# Project_Canary_V4_5.net
KiCad netlist of a schematic drawn in EAGLE
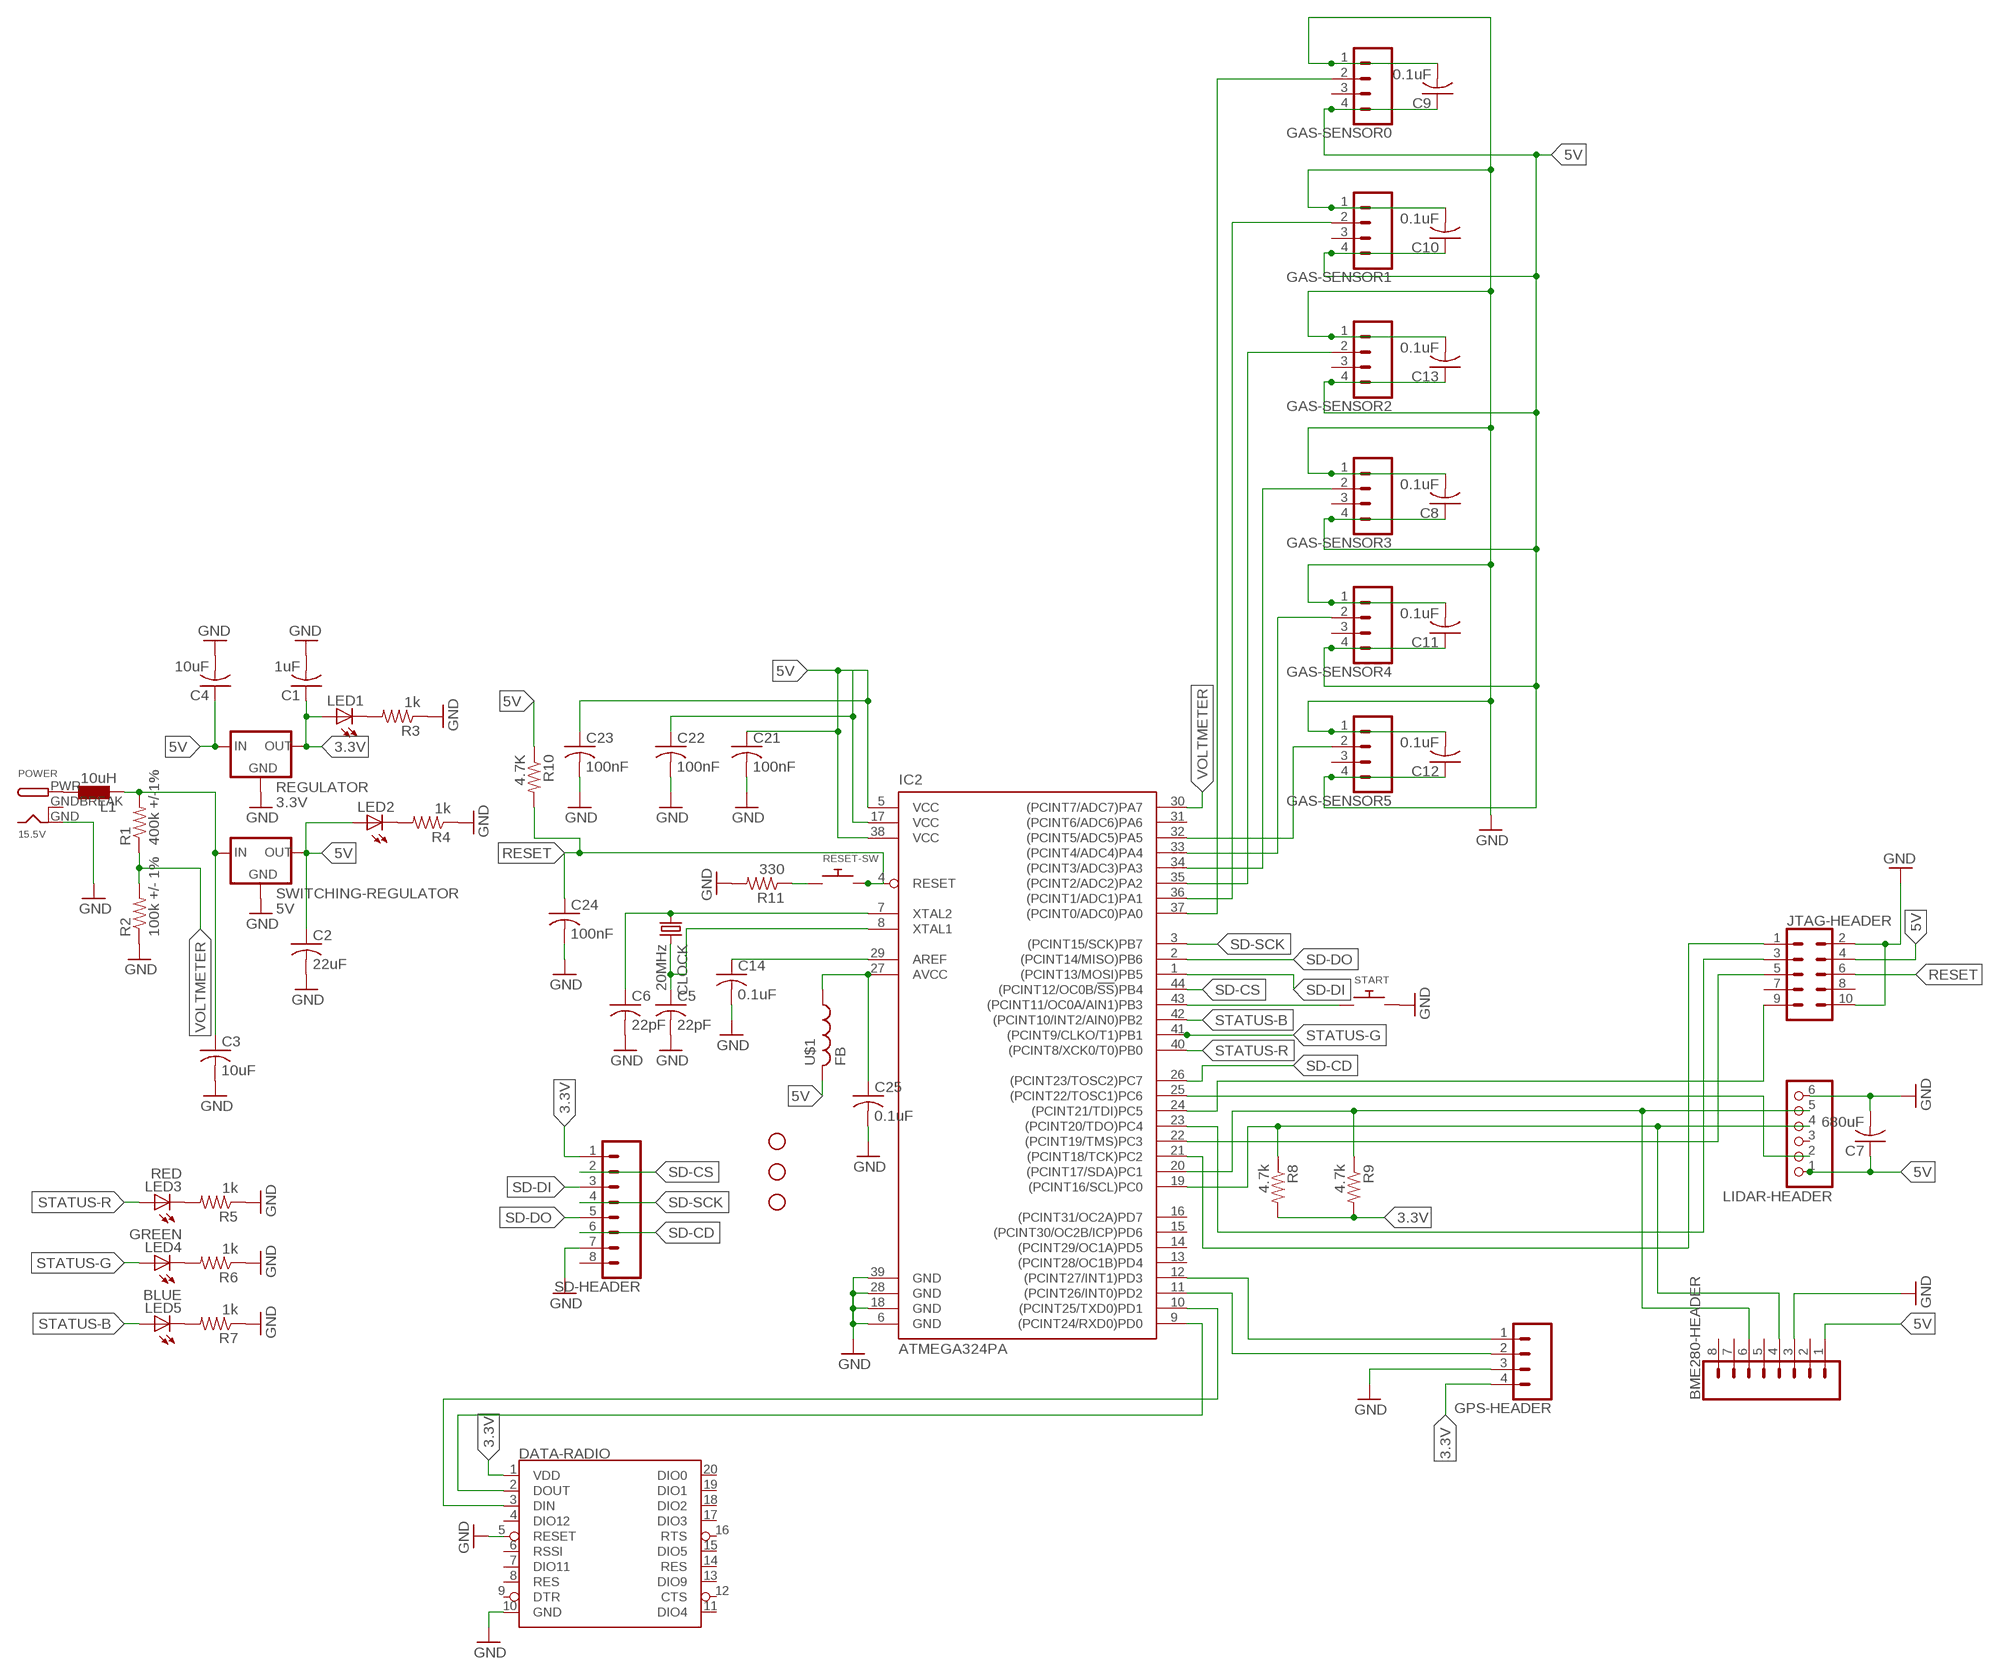
[diagram p0: schematic, sheet 1]

(export (version "E")
  (design (tool "Eeschema 10.0.6"))
  (components
    (comp (ref "BME280-HEADER")
      (value "CONN_08\"")
      (footprint "eagle-import:1X08")
      (libsource (lib "eagle-import") (part "CONN_08{dblquote}"))
    )
    (comp (ref "C1")
      (value "1uF")
      (footprint "eagle-import:C0805")
      (libsource (lib "eagle-import") (part "C-USC0805"))
    )
    (comp (ref "C2")
      (value "22uF")
      (footprint "eagle-import:C0603")
      (libsource (lib "eagle-import") (part "C-USC0603"))
    )
    (comp (ref "C3")
      (value "10uF")
      (footprint "eagle-import:C0805")
      (libsource (lib "eagle-import") (part "C-USC0805"))
    )
    (comp (ref "C4")
      (value "10uF")
      (footprint "eagle-import:C0603")
      (libsource (lib "eagle-import") (part "C-USC0603"))
    )
    (comp (ref "C5")
      (value "22pF")
      (footprint "eagle-import:C0603")
      (libsource (lib "eagle-import") (part "C-USC0603"))
    )
    (comp (ref "C6")
      (value "22pF")
      (footprint "eagle-import:C0603")
      (libsource (lib "eagle-import") (part "C-USC0603"))
    )
    (comp (ref "C7")
      (value "680uF")
      (footprint "eagle-import:C0603")
      (libsource (lib "eagle-import") (part "C-USC0603"))
    )
    (comp (ref "C8")
      (value "0.1uF")
      (footprint "eagle-import:C0603")
      (libsource (lib "eagle-import") (part "C-USC0603"))
    )
    (comp (ref "C9")
      (value "0.1uF")
      (footprint "eagle-import:C0603")
      (libsource (lib "eagle-import") (part "C-USC0603"))
    )
    (comp (ref "C10")
      (value "0.1uF")
      (footprint "eagle-import:C0603")
      (libsource (lib "eagle-import") (part "C-USC0603"))
    )
    (comp (ref "C11")
      (value "0.1uF")
      (footprint "eagle-import:C0603")
      (libsource (lib "eagle-import") (part "C-USC0603"))
    )
    (comp (ref "C12")
      (value "0.1uF")
      (footprint "eagle-import:C0603")
      (libsource (lib "eagle-import") (part "C-USC0603"))
    )
    (comp (ref "C13")
      (value "0.1uF")
      (footprint "eagle-import:C0603")
      (libsource (lib "eagle-import") (part "C-USC0603"))
    )
    (comp (ref "C14")
      (value "0.1uF")
      (footprint "eagle-import:C0603")
      (libsource (lib "eagle-import") (part "C-USC0603"))
    )
    (comp (ref "C21")
      (value "100nF")
      (footprint "eagle-import:C0603")
      (libsource (lib "eagle-import") (part "C-USC0603"))
    )
    (comp (ref "C22")
      (value "100nF")
      (footprint "eagle-import:C0603")
      (libsource (lib "eagle-import") (part "C-USC0603"))
    )
    (comp (ref "C23")
      (value "100nF")
      (footprint "eagle-import:C0603")
      (libsource (lib "eagle-import") (part "C-USC0603"))
    )
    (comp (ref "C24")
      (value "100nF")
      (footprint "eagle-import:C0805")
      (libsource (lib "eagle-import") (part "C-USC0805"))
    )
    (comp (ref "C25")
      (value "0.1uF")
      (footprint "eagle-import:C0603")
      (libsource (lib "eagle-import") (part "C-USC0603"))
    )
    (comp (ref "CLOCK")
      (value "20MHz")
      (footprint "eagle-import:86SMX")
      (libsource (lib "eagle-import") (part "CRYSTAL68SMX"))
    )
    (comp (ref "DATA-RADIO")
      (value "XBEE")
      (footprint "eagle-import:XBEE")
      (libsource (lib "eagle-import") (part "XBEE"))
    )
    (comp (ref "GAS-SENSOR0")
      (value "CONN_04")
      (footprint "eagle-import:1X04")
      (libsource (lib "eagle-import") (part "CONN_04"))
    )
    (comp (ref "GAS-SENSOR1")
      (value "CONN_04")
      (footprint "eagle-import:1X04")
      (libsource (lib "eagle-import") (part "CONN_04"))
    )
    (comp (ref "GAS-SENSOR2")
      (value "CONN_04")
      (footprint "eagle-import:1X04")
      (libsource (lib "eagle-import") (part "CONN_04"))
    )
    (comp (ref "GAS-SENSOR3")
      (value "CONN_04")
      (footprint "eagle-import:1X04")
      (libsource (lib "eagle-import") (part "CONN_04"))
    )
    (comp (ref "GAS-SENSOR4")
      (value "CONN_04")
      (footprint "eagle-import:1X04")
      (libsource (lib "eagle-import") (part "CONN_04"))
    )
    (comp (ref "GAS-SENSOR5")
      (value "CONN_04")
      (footprint "eagle-import:1X04")
      (libsource (lib "eagle-import") (part "CONN_04"))
    )
    (comp (ref "GPS-HEADER")
      (value "CONN_04")
      (footprint "eagle-import:1X04")
      (libsource (lib "eagle-import") (part "CONN_04"))
    )
    (comp (ref "IC2")
      (value "ATMEGA324PA")
      (footprint "eagle-import:TQFP44")
      (fields (field (name "MPN") "ATMEGA644PV-10AU"))
      (libsource (lib "eagle-import") (part "ATMEGA644A"))
    )
    (comp (ref "JTAG-HEADER")
      (value "CONN_05X2PTH")
      (footprint "eagle-import:2X5")
      (libsource (lib "eagle-import") (part "CONN_05X2PTH"))
    )
    (comp (ref "L1")
      (value "10uH")
      (footprint "eagle-import:L1812")
      (libsource (lib "eagle-import") (part "L"))
    )
    (comp (ref "LED1")
      (value "LEDCHIP-LED0805")
      (footprint "eagle-import:CHIP-LED0805")
      (libsource (lib "eagle-import") (part "LEDCHIP-LED0805"))
    )
    (comp (ref "LED2")
      (value "LEDCHIP-LED0805")
      (footprint "eagle-import:CHIP-LED0805")
      (libsource (lib "eagle-import") (part "LEDCHIP-LED0805"))
    )
    (comp (ref "LED3")
      (value "RED")
      (footprint "eagle-import:CHIP-LED0805")
      (libsource (lib "eagle-import") (part "LEDCHIP-LED0805"))
    )
    (comp (ref "LED4")
      (value "GREEN")
      (footprint "eagle-import:CHIP-LED0805")
      (libsource (lib "eagle-import") (part "LEDCHIP-LED0805"))
    )
    (comp (ref "LED5")
      (value "BLUE")
      (footprint "eagle-import:CHIP-LED0805")
      (libsource (lib "eagle-import") (part "LEDCHIP-LED0805"))
    )
    (comp (ref "LIDAR-HEADER")
      (value "PINHD-1X6")
      (footprint "eagle-import:1X06")
      (libsource (lib "eagle-import") (part "PINHD-1X6"))
    )
    (comp (ref "MOUNT-HOLE1")
      (value "STAND-OFF")
      (footprint "eagle-import:STAND-OFF")
      (libsource (lib "eagle-import") (part "STAND-OFF"))
    )
    (comp (ref "MOUNT-HOLE2")
      (value "STAND-OFF")
      (footprint "eagle-import:STAND-OFF")
      (libsource (lib "eagle-import") (part "STAND-OFF"))
    )
    (comp (ref "MOUNT-HOLE3")
      (value "STAND-OFF")
      (footprint "eagle-import:STAND-OFF")
      (libsource (lib "eagle-import") (part "STAND-OFF"))
    )
    (comp (ref "POWER")
      (value "15.5V")
      (footprint "eagle-import:DCJACK_2MM_PTH")
      (libsource (lib "eagle-import") (part "DCBARRELPTH"))
    )
    (comp (ref "R1")
      (value "400k +/-1%")
      (footprint "eagle-import:M0805")
      (libsource (lib "eagle-import") (part "R-US_M0805"))
    )
    (comp (ref "R2")
      (value "100k +/- 1%")
      (footprint "eagle-import:M0805")
      (libsource (lib "eagle-import") (part "R-US_M0805"))
    )
    (comp (ref "R3")
      (value "1k")
      (footprint "eagle-import:M0805")
      (libsource (lib "eagle-import") (part "R-US_M0805"))
    )
    (comp (ref "R4")
      (value "1k")
      (footprint "eagle-import:M0805")
      (libsource (lib "eagle-import") (part "R-US_M0805"))
    )
    (comp (ref "R5")
      (value "1k")
      (footprint "eagle-import:M0805")
      (libsource (lib "eagle-import") (part "R-US_M0805"))
    )
    (comp (ref "R6")
      (value "1k")
      (footprint "eagle-import:M0805")
      (libsource (lib "eagle-import") (part "R-US_M0805"))
    )
    (comp (ref "R7")
      (value "1k")
      (footprint "eagle-import:M0805")
      (libsource (lib "eagle-import") (part "R-US_M0805"))
    )
    (comp (ref "R8")
      (value "4.7k")
      (footprint "eagle-import:M0805")
      (libsource (lib "eagle-import") (part "R-US_M0805"))
    )
    (comp (ref "R9")
      (value "4.7k")
      (footprint "eagle-import:M0805")
      (libsource (lib "eagle-import") (part "R-US_M0805"))
    )
    (comp (ref "R10")
      (value "4.7K")
      (footprint "eagle-import:M0805")
      (libsource (lib "eagle-import") (part "R-US_M0805"))
    )
    (comp (ref "R11")
      (value "330")
      (footprint "eagle-import:M0805")
      (libsource (lib "eagle-import") (part "R-US_M0805"))
    )
    (comp (ref "REGULATOR")
      (value "3.3V")
      (footprint "eagle-import:TO220-IGO")
      (libsource (lib "eagle-import") (part "V_REG_78XXSINK"))
    )
    (comp (ref "RESET-SW")
      (value "SWITCH_PUSHBUTTONSOFTTOUCHSMD_SJ")
      (footprint "eagle-import:PUSHBUTTON_SMD_SJ")
      (libsource (lib "eagle-import") (part "SWITCH_PUSHBUTTONSOFTTOUCHSMD_SJ"))
    )
    (comp (ref "SD-HEADER")
      (value "CONN_08\"")
      (footprint "eagle-import:1X08")
      (libsource (lib "eagle-import") (part "CONN_08{dblquote}"))
    )
    (comp (ref "START")
      (value "SWITCH_PUSHBUTTONSOFTTOUCHSMD_SJ")
      (footprint "eagle-import:PUSHBUTTON_SMD_SJ")
      (libsource (lib "eagle-import") (part "SWITCH_PUSHBUTTONSOFTTOUCHSMD_SJ"))
    )
    (comp (ref "SWITCHING-REGULATOR")
      (value "5V")
      (footprint "eagle-import:TO220-IGO")
      (libsource (lib "eagle-import") (part "V_REG_78XXSINK"))
    )
    (comp (ref "U$1") (value "FB") (footprint "eagle-import:FB") (libsource (lib "eagle-import") (part "FB")))
  )
  (nets
    (net (code "1") (name "/GNDBREAK") (class "Default")
      (node (ref "POWER") (pin "GNDBREAK") (pinfunction "GNDBREAK_GNDBREAK") (pintype "power_in"))
    )
    (net (code "2") (name "3.3V") (class "Default")
      (node (ref "C1") (pin "1") (pinfunction "1_1") (pintype "passive"))
      (node (ref "DATA-RADIO") (pin "1") (pinfunction "VDD_1") (pintype "power_in"))
      (node (ref "GPS-HEADER") (pin "4") (pinfunction "4_4") (pintype "passive"))
      (node (ref "LED1") (pin "A") (pinfunction "A_A") (pintype "passive"))
      (node (ref "R8") (pin "2") (pinfunction "2_2") (pintype "passive"))
      (node (ref "R9") (pin "2") (pinfunction "2_2") (pintype "passive"))
      (node (ref "REGULATOR") (pin "OUT") (pinfunction "OUT_OUT") (pintype "passive"))
      (node (ref "SD-HEADER") (pin "1") (pinfunction "1_1") (pintype "passive"))
    )
    (net (code "3") (name "5V") (class "Default")
      (node (ref "BME280-HEADER") (pin "1") (pinfunction "1_1") (pintype "passive"))
      (node (ref "C10") (pin "1") (pinfunction "1_1") (pintype "passive"))
      (node (ref "C11") (pin "1") (pinfunction "1_1") (pintype "passive"))
      (node (ref "C12") (pin "1") (pinfunction "1_1") (pintype "passive"))
      (node (ref "C13") (pin "1") (pinfunction "1_1") (pintype "passive"))
      (node (ref "C2") (pin "1") (pinfunction "1_1") (pintype "passive"))
      (node (ref "C21") (pin "1") (pinfunction "1_1") (pintype "passive"))
      (node (ref "C22") (pin "1") (pinfunction "1_1") (pintype "passive"))
      (node (ref "C23") (pin "1") (pinfunction "1_1") (pintype "passive"))
      (node (ref "C25") (pin "1") (pinfunction "1_1") (pintype "passive"))
      (node (ref "C4") (pin "1") (pinfunction "1_1") (pintype "passive"))
      (node (ref "C7") (pin "1") (pinfunction "1_1") (pintype "passive"))
      (node (ref "C8") (pin "1") (pinfunction "1_1") (pintype "passive"))
      (node (ref "C9") (pin "1") (pinfunction "1_1") (pintype "passive"))
      (node (ref "GAS-SENSOR0") (pin "4") (pinfunction "4_4") (pintype "passive"))
      (node (ref "GAS-SENSOR1") (pin "4") (pinfunction "4_4") (pintype "passive"))
      (node (ref "GAS-SENSOR2") (pin "4") (pinfunction "4_4") (pintype "passive"))
      (node (ref "GAS-SENSOR3") (pin "4") (pinfunction "4_4") (pintype "passive"))
      (node (ref "GAS-SENSOR4") (pin "4") (pinfunction "4_4") (pintype "passive"))
      (node (ref "GAS-SENSOR5") (pin "4") (pinfunction "4_4") (pintype "passive"))
      (node (ref "IC2") (pin "17") (pinfunction "VCC_17") (pintype "power_in"))
      (node (ref "IC2") (pin "27") (pinfunction "AVCC_27") (pintype "power_in"))
      (node (ref "IC2") (pin "38") (pinfunction "VCC_38") (pintype "power_in"))
      (node (ref "IC2") (pin "5") (pinfunction "VCC_5") (pintype "power_in"))
      (node (ref "JTAG-HEADER") (pin "4") (pinfunction "4_4") (pintype "passive"))
      (node (ref "LED2") (pin "A") (pinfunction "A_A") (pintype "passive"))
      (node (ref "LIDAR-HEADER") (pin "1") (pinfunction "1_1") (pintype "passive"))
      (node (ref "REGULATOR") (pin "IN") (pinfunction "IN_IN") (pintype "input"))
      (node (ref "SWITCHING-REGULATOR") (pin "OUT") (pinfunction "OUT_OUT") (pintype "passive"))
      (node (ref "U$1") (pin "P$1") (pinfunction "1_P$1") (pintype "passive"))
    )
    (net (code "4") (name "GND") (class "Default")
      (node (ref "BME280-HEADER") (pin "3") (pinfunction "3_3") (pintype "passive"))
      (node (ref "C1") (pin "2") (pinfunction "2_2") (pintype "passive"))
      (node (ref "C10") (pin "2") (pinfunction "2_2") (pintype "passive"))
      (node (ref "C11") (pin "2") (pinfunction "2_2") (pintype "passive"))
      (node (ref "C12") (pin "2") (pinfunction "2_2") (pintype "passive"))
      (node (ref "C13") (pin "2") (pinfunction "2_2") (pintype "passive"))
      (node (ref "C14") (pin "2") (pinfunction "2_2") (pintype "passive"))
      (node (ref "C2") (pin "2") (pinfunction "2_2") (pintype "passive"))
      (node (ref "C21") (pin "2") (pinfunction "2_2") (pintype "passive"))
      (node (ref "C22") (pin "2") (pinfunction "2_2") (pintype "passive"))
      (node (ref "C23") (pin "2") (pinfunction "2_2") (pintype "passive"))
      (node (ref "C24") (pin "2") (pinfunction "2_2") (pintype "passive"))
      (node (ref "C25") (pin "2") (pinfunction "2_2") (pintype "passive"))
      (node (ref "C3") (pin "2") (pinfunction "2_2") (pintype "passive"))
      (node (ref "C4") (pin "2") (pinfunction "2_2") (pintype "passive"))
      (node (ref "C5") (pin "2") (pinfunction "2_2") (pintype "passive"))
      (node (ref "C6") (pin "2") (pinfunction "2_2") (pintype "passive"))
      (node (ref "C7") (pin "2") (pinfunction "2_2") (pintype "passive"))
      (node (ref "C8") (pin "2") (pinfunction "2_2") (pintype "passive"))
      (node (ref "C9") (pin "2") (pinfunction "2_2") (pintype "passive"))
      (node (ref "DATA-RADIO") (pin "10") (pinfunction "GND_10") (pintype "power_in"))
      (node (ref "DATA-RADIO") (pin "5") (pinfunction "RESET_5") (pintype "input"))
      (node (ref "GAS-SENSOR0") (pin "1") (pinfunction "1_1") (pintype "passive"))
      (node (ref "GAS-SENSOR1") (pin "1") (pinfunction "1_1") (pintype "passive"))
      (node (ref "GAS-SENSOR2") (pin "1") (pinfunction "1_1") (pintype "passive"))
      (node (ref "GAS-SENSOR3") (pin "1") (pinfunction "1_1") (pintype "passive"))
      (node (ref "GAS-SENSOR4") (pin "1") (pinfunction "1_1") (pintype "passive"))
      (node (ref "GAS-SENSOR5") (pin "1") (pinfunction "1_1") (pintype "passive"))
      (node (ref "GPS-HEADER") (pin "3") (pinfunction "3_3") (pintype "passive"))
      (node (ref "IC2") (pin "18") (pinfunction "GND_18") (pintype "power_in"))
      (node (ref "IC2") (pin "28") (pinfunction "GND_28") (pintype "power_in"))
      (node (ref "IC2") (pin "39") (pinfunction "GND_39") (pintype "power_in"))
      (node (ref "IC2") (pin "6") (pinfunction "GND_6") (pintype "power_in"))
      (node (ref "JTAG-HEADER") (pin "10") (pinfunction "10_10") (pintype "passive"))
      (node (ref "JTAG-HEADER") (pin "2") (pinfunction "2_2") (pintype "passive"))
      (node (ref "LIDAR-HEADER") (pin "6") (pinfunction "6_6") (pintype "passive"))
      (node (ref "POWER") (pin "GND") (pinfunction "GND_GND") (pintype "power_in"))
      (node (ref "R11") (pin "2") (pinfunction "2_2") (pintype "passive"))
      (node (ref "R2") (pin "1") (pinfunction "1_1") (pintype "passive"))
      (node (ref "R3") (pin "1") (pinfunction "1_1") (pintype "passive"))
      (node (ref "R4") (pin "1") (pinfunction "1_1") (pintype "passive"))
      (node (ref "R5") (pin "1") (pinfunction "1_1") (pintype "passive"))
      (node (ref "R6") (pin "1") (pinfunction "1_1") (pintype "passive"))
      (node (ref "R7") (pin "1") (pinfunction "1_1") (pintype "passive"))
      (node (ref "REGULATOR") (pin "GND") (pinfunction "GND_GND") (pintype "input"))
      (node (ref "SD-HEADER") (pin "7") (pinfunction "7_7") (pintype "passive"))
      (node (ref "START") (pin "P$2") (pinfunction "P$2_P$2") (pintype "passive"))
      (node (ref "SWITCHING-REGULATOR") (pin "GND") (pinfunction "GND_GND") (pintype "input"))
    )
    (net (code "5") (name "Net-(C3-Pad1)") (class "Default")
      (node (ref "C3") (pin "1") (pinfunction "1_1") (pintype "passive"))
      (node (ref "L1") (pin "2") (pinfunction "2_2") (pintype "passive"))
      (node (ref "R1") (pin "2") (pinfunction "2_2") (pintype "passive"))
      (node (ref "SWITCHING-REGULATOR") (pin "IN") (pinfunction "IN_IN") (pintype "input"))
    )
    (net (code "6") (name "Net-(CLOCK-2)") (class "Default")
      (node (ref "C5") (pin "1") (pinfunction "1_1") (pintype "passive"))
      (node (ref "CLOCK") (pin "4") (pinfunction "2_4") (pintype "passive"))
      (node (ref "IC2") (pin "8") (pinfunction "XTAL1_8") (pintype "bidirectional"))
    )
    (net (code "7") (name "Net-(DATA-RADIO-DIN)") (class "Default")
      (node (ref "DATA-RADIO") (pin "3") (pinfunction "DIN_3") (pintype "input"))
      (node (ref "IC2") (pin "10") (pinfunction "(PCINT25/TXD0)PD1_10") (pintype "bidirectional"))
    )
    (net (code "8") (name "Net-(DATA-RADIO-DOUT)") (class "Default")
      (node (ref "DATA-RADIO") (pin "2") (pinfunction "DOUT_2") (pintype "output"))
      (node (ref "IC2") (pin "9") (pinfunction "(PCINT24/RXD0)PD0_9") (pintype "bidirectional"))
    )
    (net (code "9") (name "Net-(IC2-(PCINT0{slash}ADC0)PA0)") (class "Default")
      (node (ref "GAS-SENSOR0") (pin "2") (pinfunction "2_2") (pintype "passive"))
      (node (ref "IC2") (pin "37") (pinfunction "(PCINT0/ADC0)PA0_37") (pintype "bidirectional"))
    )
    (net (code "10") (name "Net-(IC2-(PCINT1{slash}ADC1)PA1)") (class "Default")
      (node (ref "GAS-SENSOR1") (pin "2") (pinfunction "2_2") (pintype "passive"))
      (node (ref "IC2") (pin "36") (pinfunction "(PCINT1/ADC1)PA1_36") (pintype "bidirectional"))
    )
    (net (code "11") (name "Net-(IC2-(PCINT2{slash}ADC2)PA2)") (class "Default")
      (node (ref "GAS-SENSOR2") (pin "2") (pinfunction "2_2") (pintype "passive"))
      (node (ref "IC2") (pin "35") (pinfunction "(PCINT2/ADC2)PA2_35") (pintype "bidirectional"))
    )
    (net (code "12") (name "Net-(IC2-(PCINT3{slash}ADC3)PA3)") (class "Default")
      (node (ref "GAS-SENSOR3") (pin "2") (pinfunction "2_2") (pintype "passive"))
      (node (ref "IC2") (pin "34") (pinfunction "(PCINT3/ADC3)PA3_34") (pintype "bidirectional"))
    )
    (net (code "13") (name "Net-(IC2-(PCINT4{slash}ADC4)PA4)") (class "Default")
      (node (ref "GAS-SENSOR4") (pin "2") (pinfunction "2_2") (pintype "passive"))
      (node (ref "IC2") (pin "33") (pinfunction "(PCINT4/ADC4)PA4_33") (pintype "bidirectional"))
    )
    (net (code "14") (name "Net-(IC2-(PCINT5{slash}ADC5)PA5)") (class "Default")
      (node (ref "GAS-SENSOR5") (pin "2") (pinfunction "2_2") (pintype "passive"))
      (node (ref "IC2") (pin "32") (pinfunction "(PCINT5/ADC5)PA5_32") (pintype "bidirectional"))
    )
    (net (code "15") (name "Net-(IC2-(PCINT11{slash}OC0A{slash}AIN1)PB3)") (class "Default")
      (node (ref "IC2") (pin "43") (pinfunction "(PCINT11/OC0A/AIN1)PB3_43") (pintype "bidirectional"))
      (node (ref "START") (pin "P$1") (pinfunction "P$1_P$1") (pintype "passive"))
    )
    (net (code "16") (name "Net-(IC2-(PCINT16{slash}SCL)PC0)") (class "Default")
      (node (ref "BME280-HEADER") (pin "4") (pinfunction "4_4") (pintype "passive"))
      (node (ref "IC2") (pin "19") (pinfunction "(PCINT16/SCL)PC0_19") (pintype "output"))
      (node (ref "LIDAR-HEADER") (pin "4") (pinfunction "4_4") (pintype "passive"))
      (node (ref "R8") (pin "1") (pinfunction "1_1") (pintype "passive"))
    )
    (net (code "17") (name "Net-(IC2-(PCINT17{slash}SDA)PC1)") (class "Default")
      (node (ref "BME280-HEADER") (pin "6") (pinfunction "6_6") (pintype "passive"))
      (node (ref "IC2") (pin "20") (pinfunction "(PCINT17/SDA)PC1_20") (pintype "output"))
      (node (ref "LIDAR-HEADER") (pin "5") (pinfunction "5_5") (pintype "passive"))
      (node (ref "R9") (pin "1") (pinfunction "1_1") (pintype "passive"))
    )
    (net (code "18") (name "Net-(IC2-(PCINT18{slash}TCK)PC2)") (class "Default")
      (node (ref "IC2") (pin "21") (pinfunction "(PCINT18/TCK)PC2_21") (pintype "output"))
      (node (ref "JTAG-HEADER") (pin "1") (pinfunction "1_1") (pintype "passive"))
    )
    (net (code "19") (name "Net-(IC2-(PCINT19{slash}TMS)PC3)") (class "Default")
      (node (ref "IC2") (pin "22") (pinfunction "(PCINT19/TMS)PC3_22") (pintype "output"))
      (node (ref "JTAG-HEADER") (pin "5") (pinfunction "5_5") (pintype "passive"))
    )
    (net (code "20") (name "Net-(IC2-(PCINT20{slash}TDO)PC4)") (class "Default")
      (node (ref "IC2") (pin "23") (pinfunction "(PCINT20/TDO)PC4_23") (pintype "output"))
      (node (ref "JTAG-HEADER") (pin "3") (pinfunction "3_3") (pintype "passive"))
    )
    (net (code "21") (name "Net-(IC2-(PCINT21{slash}TDI)PC5)") (class "Default")
      (node (ref "IC2") (pin "24") (pinfunction "(PCINT21/TDI)PC5_24") (pintype "output"))
      (node (ref "JTAG-HEADER") (pin "9") (pinfunction "9_9") (pintype "passive"))
    )
    (net (code "22") (name "Net-(IC2-(PCINT22{slash}TOSC1)PC6)") (class "Default")
      (node (ref "IC2") (pin "25") (pinfunction "(PCINT22/TOSC1)PC6_25") (pintype "output"))
      (node (ref "LIDAR-HEADER") (pin "2") (pinfunction "2_2") (pintype "passive"))
    )
    (net (code "23") (name "Net-(IC2-(PCINT26{slash}INT0)PD2)") (class "Default")
      (node (ref "GPS-HEADER") (pin "2") (pinfunction "2_2") (pintype "passive"))
      (node (ref "IC2") (pin "11") (pinfunction "(PCINT26/INT0)PD2_11") (pintype "bidirectional"))
    )
    (net (code "24") (name "Net-(IC2-(PCINT27{slash}INT1)PD3)") (class "Default")
      (node (ref "GPS-HEADER") (pin "1") (pinfunction "1_1") (pintype "passive"))
      (node (ref "IC2") (pin "12") (pinfunction "(PCINT27/INT1)PD3_12") (pintype "bidirectional"))
    )
    (net (code "25") (name "Net-(IC2-AREF)") (class "Default")
      (node (ref "C14") (pin "1") (pinfunction "1_1") (pintype "passive"))
      (node (ref "IC2") (pin "29") (pinfunction "AREF_29") (pintype "passive"))
    )
    (net (code "26") (name "Net-(IC2-XTAL2)") (class "Default")
      (node (ref "C6") (pin "1") (pinfunction "1_1") (pintype "passive"))
      (node (ref "CLOCK") (pin "1") (pinfunction "1_1") (pintype "passive"))
      (node (ref "IC2") (pin "7") (pinfunction "XTAL2_7") (pintype "bidirectional"))
    )
    (net (code "27") (name "Net-(L1-Pad1)") (class "Default")
      (node (ref "L1") (pin "1") (pinfunction "1_1") (pintype "passive"))
      (node (ref "POWER") (pin "PWR") (pinfunction "PWR_PWR") (pintype "power_in"))
    )
    (net (code "28") (name "Net-(LED1-PadC)") (class "Default")
      (node (ref "LED1") (pin "C") (pinfunction "C_C") (pintype "passive"))
      (node (ref "R3") (pin "2") (pinfunction "2_2") (pintype "passive"))
    )
    (net (code "29") (name "Net-(LED2-PadC)") (class "Default")
      (node (ref "LED2") (pin "C") (pinfunction "C_C") (pintype "passive"))
      (node (ref "R4") (pin "2") (pinfunction "2_2") (pintype "passive"))
    )
    (net (code "30") (name "Net-(LED3-PadC)") (class "Default")
      (node (ref "LED3") (pin "C") (pinfunction "C_C") (pintype "passive"))
      (node (ref "R5") (pin "2") (pinfunction "2_2") (pintype "passive"))
    )
    (net (code "31") (name "Net-(LED4-PadC)") (class "Default")
      (node (ref "LED4") (pin "C") (pinfunction "C_C") (pintype "passive"))
      (node (ref "R6") (pin "2") (pinfunction "2_2") (pintype "passive"))
    )
    (net (code "32") (name "Net-(LED5-PadC)") (class "Default")
      (node (ref "LED5") (pin "C") (pinfunction "C_C") (pintype "passive"))
      (node (ref "R7") (pin "2") (pinfunction "2_2") (pintype "passive"))
    )
    (net (code "33") (name "Net-(R11-Pad1)") (class "Default")
      (node (ref "R11") (pin "1") (pinfunction "1_1") (pintype "passive"))
      (node (ref "RESET-SW") (pin "P$1") (pinfunction "P$1_P$1") (pintype "passive"))
    )
    (net (code "34") (name "RESET") (class "Default")
      (node (ref "C24") (pin "1") (pinfunction "1_1") (pintype "passive"))
      (node (ref "IC2") (pin "4") (pinfunction "RESET_4") (pintype "input"))
      (node (ref "JTAG-HEADER") (pin "6") (pinfunction "6_6") (pintype "passive"))
      (node (ref "R10") (pin "2") (pinfunction "2_2") (pintype "passive"))
      (node (ref "RESET-SW") (pin "P$2") (pinfunction "P$2_P$2") (pintype "passive"))
    )
    (net (code "35") (name "SD-CD") (class "Default")
      (node (ref "IC2") (pin "26") (pinfunction "(PCINT23/TOSC2)PC7_26") (pintype "output"))
      (node (ref "SD-HEADER") (pin "6") (pinfunction "6_6") (pintype "passive"))
    )
    (net (code "36") (name "SD-CS") (class "Default")
      (node (ref "IC2") (pin "44") (pinfunction "(PCINT12/OC0B/~{SS})PB4_44") (pintype "bidirectional"))
      (node (ref "SD-HEADER") (pin "2") (pinfunction "2_2") (pintype "passive"))
    )
    (net (code "37") (name "SD-DI") (class "Default")
      (node (ref "IC2") (pin "1") (pinfunction "(PCINT13/MOSI)PB5_1") (pintype "bidirectional"))
      (node (ref "SD-HEADER") (pin "3") (pinfunction "3_3") (pintype "passive"))
    )
    (net (code "38") (name "SD-DO") (class "Default")
      (node (ref "IC2") (pin "2") (pinfunction "(PCINT14/MISO)PB6_2") (pintype "bidirectional"))
      (node (ref "SD-HEADER") (pin "5") (pinfunction "5_5") (pintype "passive"))
    )
    (net (code "39") (name "SD-SCK") (class "Default")
      (node (ref "IC2") (pin "3") (pinfunction "(PCINT15/SCK)PB7_3") (pintype "bidirectional"))
      (node (ref "SD-HEADER") (pin "4") (pinfunction "4_4") (pintype "passive"))
    )
    (net (code "40") (name "STATUS-B") (class "Default")
      (node (ref "IC2") (pin "42") (pinfunction "(PCINT10/INT2/AIN0)PB2_42") (pintype "bidirectional"))
      (node (ref "LED5") (pin "A") (pinfunction "A_A") (pintype "passive"))
    )
    (net (code "41") (name "STATUS-G") (class "Default")
      (node (ref "IC2") (pin "41") (pinfunction "(PCINT9/CLKO/T1)PB1_41") (pintype "bidirectional"))
      (node (ref "LED4") (pin "A") (pinfunction "A_A") (pintype "passive"))
    )
    (net (code "42") (name "STATUS-R") (class "Default")
      (node (ref "IC2") (pin "40") (pinfunction "(PCINT8/XCK0/T0)PB0_40") (pintype "bidirectional"))
      (node (ref "LED3") (pin "A") (pinfunction "A_A") (pintype "passive"))
    )
    (net (code "43") (name "VOLTMETER") (class "Default")
      (node (ref "IC2") (pin "30") (pinfunction "(PCINT7/ADC7)PA7_30") (pintype "bidirectional"))
      (node (ref "R1") (pin "1") (pinfunction "1_1") (pintype "passive"))
      (node (ref "R2") (pin "2") (pinfunction "2_2") (pintype "passive"))
    )
    (net (code "44") (name "unconnected-(BME280-HEADER-Pad2)") (class "Default")
      (node (ref "BME280-HEADER") (pin "2") (pinfunction "2_2") (pintype "passive"))
    )
    (net (code "45") (name "unconnected-(BME280-HEADER-Pad5)") (class "Default")
      (node (ref "BME280-HEADER") (pin "5") (pinfunction "5_5") (pintype "passive"))
    )
    (net (code "46") (name "unconnected-(BME280-HEADER-Pad7)") (class "Default")
      (node (ref "BME280-HEADER") (pin "7") (pinfunction "7_7") (pintype "passive"))
    )
    (net (code "47") (name "unconnected-(BME280-HEADER-Pad8)") (class "Default")
      (node (ref "BME280-HEADER") (pin "8") (pinfunction "8_8") (pintype "passive"))
    )
    (net (code "48") (name "unconnected-(DATA-RADIO-CTS-Pad12)") (class "Default")
      (node (ref "DATA-RADIO") (pin "12") (pinfunction "CTS_12") (pintype "output"))
    )
    (net (code "49") (name "unconnected-(DATA-RADIO-DIO0-Pad20)") (class "Default")
      (node (ref "DATA-RADIO") (pin "20") (pinfunction "DIO0_20") (pintype "bidirectional"))
    )
    (net (code "50") (name "unconnected-(DATA-RADIO-DIO1-Pad19)") (class "Default")
      (node (ref "DATA-RADIO") (pin "19") (pinfunction "DIO1_19") (pintype "bidirectional"))
    )
    (net (code "51") (name "unconnected-(DATA-RADIO-DIO2-Pad18)") (class "Default")
      (node (ref "DATA-RADIO") (pin "18") (pinfunction "DIO2_18") (pintype "bidirectional"))
    )
    (net (code "52") (name "unconnected-(DATA-RADIO-DIO3-Pad17)") (class "Default")
      (node (ref "DATA-RADIO") (pin "17") (pinfunction "DIO3_17") (pintype "bidirectional"))
    )
    (net (code "53") (name "unconnected-(DATA-RADIO-DIO4-Pad11)") (class "Default")
      (node (ref "DATA-RADIO") (pin "11") (pinfunction "DIO4_11") (pintype "bidirectional"))
    )
    (net (code "54") (name "unconnected-(DATA-RADIO-DIO5-Pad15)") (class "Default")
      (node (ref "DATA-RADIO") (pin "15") (pinfunction "DIO5_15") (pintype "bidirectional"))
    )
    (net (code "55") (name "unconnected-(DATA-RADIO-DIO9-Pad13)") (class "Default")
      (node (ref "DATA-RADIO") (pin "13") (pinfunction "DIO9_13") (pintype "bidirectional"))
    )
    (net (code "56") (name "unconnected-(DATA-RADIO-DIO11-Pad7)") (class "Default")
      (node (ref "DATA-RADIO") (pin "7") (pinfunction "DIO11_7") (pintype "bidirectional"))
    )
    (net (code "57") (name "unconnected-(DATA-RADIO-DIO12-Pad4)") (class "Default")
      (node (ref "DATA-RADIO") (pin "4") (pinfunction "DIO12_4") (pintype "bidirectional"))
    )
    (net (code "58") (name "unconnected-(DATA-RADIO-DTR-Pad9)") (class "Default")
      (node (ref "DATA-RADIO") (pin "9") (pinfunction "DTR_9") (pintype "bidirectional"))
    )
    (net (code "59") (name "unconnected-(DATA-RADIO-RES-Pad8)") (class "Default")
      (node (ref "DATA-RADIO") (pin "8") (pinfunction "RES_8") (pintype "bidirectional"))
    )
    (net (code "60") (name "unconnected-(DATA-RADIO-RES-Pad14)") (class "Default")
      (node (ref "DATA-RADIO") (pin "14") (pinfunction "RES_14") (pintype "bidirectional"))
    )
    (net (code "61") (name "unconnected-(DATA-RADIO-RSSI-Pad6)") (class "Default")
      (node (ref "DATA-RADIO") (pin "6") (pinfunction "RSSI_6") (pintype "bidirectional"))
    )
    (net (code "62") (name "unconnected-(DATA-RADIO-RTS-Pad16)") (class "Default")
      (node (ref "DATA-RADIO") (pin "16") (pinfunction "RTS_16") (pintype "input"))
    )
    (net (code "63") (name "unconnected-(GAS-SENSOR0-Pad3)") (class "Default")
      (node (ref "GAS-SENSOR0") (pin "3") (pinfunction "3_3") (pintype "passive"))
    )
    (net (code "64") (name "unconnected-(GAS-SENSOR1-Pad3)") (class "Default")
      (node (ref "GAS-SENSOR1") (pin "3") (pinfunction "3_3") (pintype "passive"))
    )
    (net (code "65") (name "unconnected-(GAS-SENSOR2-Pad3)") (class "Default")
      (node (ref "GAS-SENSOR2") (pin "3") (pinfunction "3_3") (pintype "passive"))
    )
    (net (code "66") (name "unconnected-(GAS-SENSOR3-Pad3)") (class "Default")
      (node (ref "GAS-SENSOR3") (pin "3") (pinfunction "3_3") (pintype "passive"))
    )
    (net (code "67") (name "unconnected-(GAS-SENSOR4-Pad3)") (class "Default")
      (node (ref "GAS-SENSOR4") (pin "3") (pinfunction "3_3") (pintype "passive"))
    )
    (net (code "68") (name "unconnected-(GAS-SENSOR5-Pad3)") (class "Default")
      (node (ref "GAS-SENSOR5") (pin "3") (pinfunction "3_3") (pintype "passive"))
    )
    (net (code "69") (name "unconnected-(IC2-(PCINT6{slash}ADC6)PA6-Pad31)") (class "Default")
      (node (ref "IC2") (pin "31") (pinfunction "(PCINT6/ADC6)PA6_31") (pintype "bidirectional"))
    )
    (net (code "70") (name "unconnected-(IC2-(PCINT28{slash}OC1B)PD4-Pad13)") (class "Default")
      (node (ref "IC2") (pin "13") (pinfunction "(PCINT28/OC1B)PD4_13") (pintype "bidirectional"))
    )
    (net (code "71") (name "unconnected-(IC2-(PCINT29{slash}OC1A)PD5-Pad14)") (class "Default")
      (node (ref "IC2") (pin "14") (pinfunction "(PCINT29/OC1A)PD5_14") (pintype "bidirectional"))
    )
    (net (code "72") (name "unconnected-(IC2-(PCINT30{slash}OC2B{slash}ICP)PD6-Pad15)") (class "Default")
      (node (ref "IC2") (pin "15") (pinfunction "(PCINT30/OC2B/ICP)PD6_15") (pintype "bidirectional"))
    )
    (net (code "73") (name "unconnected-(IC2-(PCINT31{slash}OC2A)PD7-Pad16)") (class "Default")
      (node (ref "IC2") (pin "16") (pinfunction "(PCINT31/OC2A)PD7_16") (pintype "bidirectional"))
    )
    (net (code "74") (name "unconnected-(JTAG-HEADER-Pad7)") (class "Default")
      (node (ref "JTAG-HEADER") (pin "7") (pinfunction "7_7") (pintype "passive"))
    )
    (net (code "75") (name "unconnected-(JTAG-HEADER-Pad8)") (class "Default")
      (node (ref "JTAG-HEADER") (pin "8") (pinfunction "8_8") (pintype "passive"))
    )
    (net (code "76") (name "unconnected-(LIDAR-HEADER-Pad3)") (class "Default")
      (node (ref "LIDAR-HEADER") (pin "3") (pinfunction "3_3") (pintype "passive"))
    )
    (net (code "77") (name "unconnected-(R10-Pad1)") (class "Default")
      (node (ref "R10") (pin "1") (pinfunction "1_1") (pintype "passive"))
    )
    (net (code "78") (name "unconnected-(SD-HEADER-Pad8)") (class "Default")
      (node (ref "SD-HEADER") (pin "8") (pinfunction "8_8") (pintype "passive"))
    )
    (net (code "79") (name "unconnected-(U$1-2-PadP$2)") (class "Default")
      (node (ref "U$1") (pin "P$2") (pinfunction "2_P$2") (pintype "passive"))
    )
  )
)
